# lsm_cpu.net
KiCad netlist of a schematic drawn in EAGLE
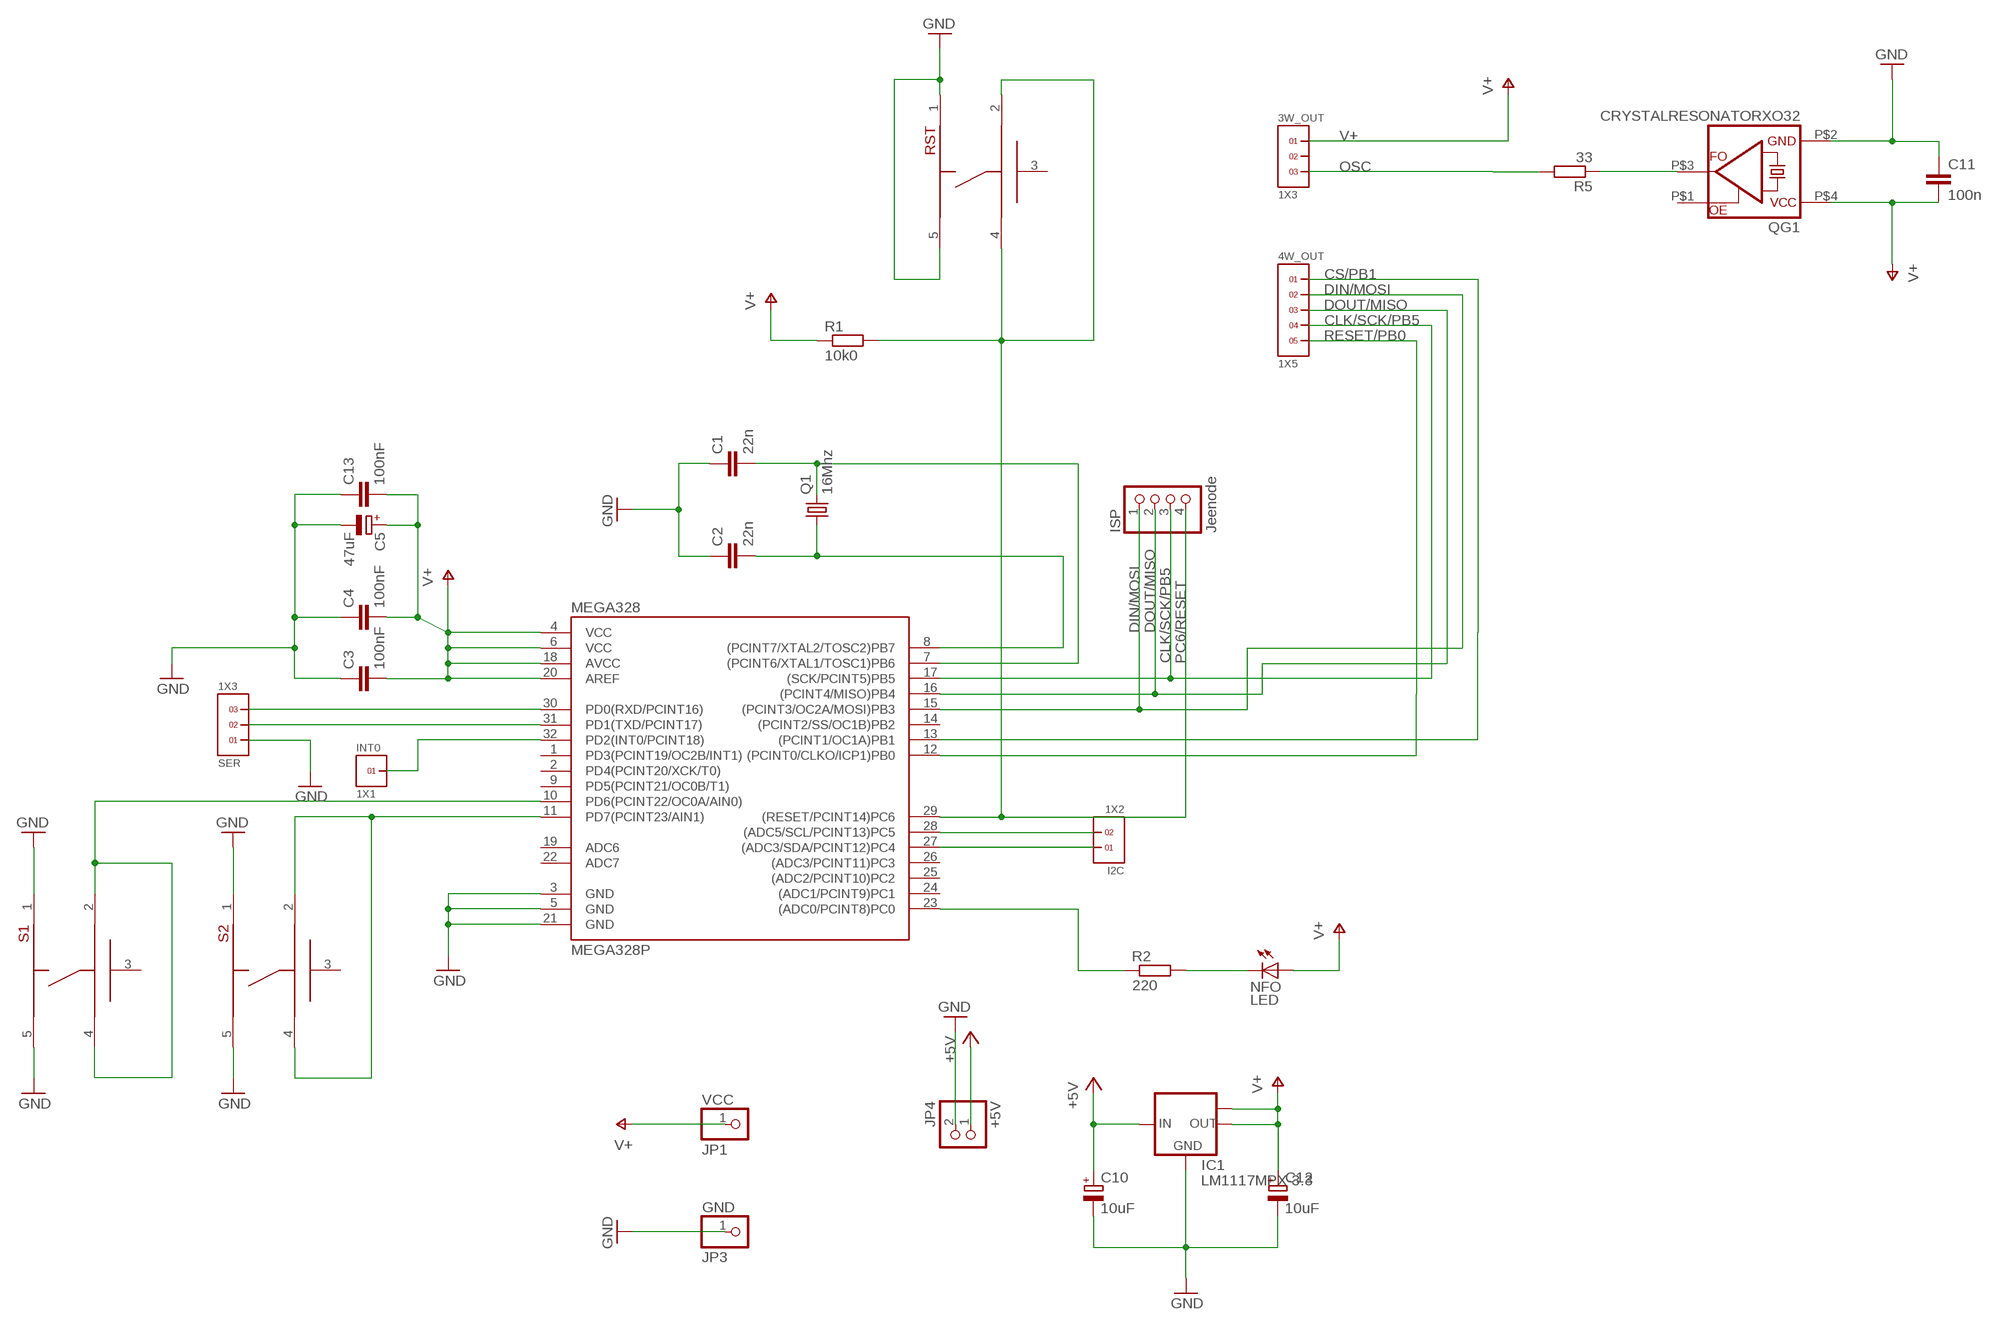
[diagram p0: schematic, sheet 1]

(export (version "E")
  (design (tool "Eeschema 10.0.6"))
  (components
    (comp (ref "+5V")
      (value "JP4")
      (footprint "eagle-import:1X02")
      (libsource (lib "eagle-import") (part "PINHD-1X2"))
    )
    (comp (ref "3W_OUT")
      (value "1X3")
      (footprint "eagle-import:1X3")
      (libsource (lib "eagle-import") (part "1X3"))
    )
    (comp (ref "4W_OUT")
      (value "1X5")
      (footprint "eagle-import:1X5")
      (libsource (lib "eagle-import") (part "1X5"))
    )
    (comp (ref "C1")
      (value "22n")
      (footprint "eagle-import:C1206")
      (libsource (lib "eagle-import") (part "C-EUC1206"))
    )
    (comp (ref "C2")
      (value "22n")
      (footprint "eagle-import:C1206")
      (libsource (lib "eagle-import") (part "C-EUC1206"))
    )
    (comp (ref "C3")
      (value "100nF")
      (footprint "eagle-import:C1206")
      (libsource (lib "eagle-import") (part "C-EUC1206"))
    )
    (comp (ref "C4")
      (value "100nF")
      (footprint "eagle-import:C1206")
      (libsource (lib "eagle-import") (part "C-EUC1206"))
    )
    (comp (ref "C5")
      (value "47uF")
      (footprint "eagle-import:E2-4")
      (libsource (lib "eagle-import") (part "CPOL-EUE2-4"))
    )
    (comp (ref "C10")
      (value "10uF")
      (footprint "eagle-import:E2-4")
      (libsource (lib "eagle-import") (part "CPOL-EUE2-4"))
    )
    (comp (ref "C11")
      (value "100n")
      (footprint "eagle-import:C1206")
      (libsource (lib "eagle-import") (part "C-EUC1206"))
    )
    (comp (ref "C12")
      (value "10uF")
      (footprint "eagle-import:E2-4")
      (libsource (lib "eagle-import") (part "CPOL-EUE2-4"))
    )
    (comp (ref "C13")
      (value "100nF")
      (footprint "eagle-import:C1206")
      (libsource (lib "eagle-import") (part "C-EUC1206"))
    )
    (comp (ref "GND")
      (value "JP3")
      (footprint "eagle-import:1X01")
      (libsource (lib "eagle-import") (part "PINHD-1X1"))
    )
    (comp (ref "I2C")
      (value "1X2")
      (footprint "eagle-import:1X2")
      (libsource (lib "eagle-import") (part "1X2"))
    )
    (comp (ref "IC1")
      (value "LM1117MPX-3.3")
      (footprint "eagle-import:SOT223")
      (libsource (lib "eagle-import") (part "LM1117MPX-3.3"))
    )
    (comp (ref "INT0")
      (value "1X1")
      (footprint "eagle-import:1X1")
      (libsource (lib "eagle-import") (part "1X1"))
    )
    (comp (ref "ISP")
      (value "Jeenode")
      (footprint "eagle-import:1X04")
      (libsource (lib "eagle-import") (part "PINHD-1X4"))
    )
    (comp (ref "MEGA328")
      (value "MEGA328P")
      (footprint "eagle-import:TQFP32-08")
      (libsource (lib "eagle-import") (part "MEGA328P"))
    )
    (comp (ref "NFO")
      (value "LED")
      (footprint "eagle-import:SML1206")
      (libsource (lib "eagle-import") (part "LEDSML1206"))
    )
    (comp (ref "Q1")
      (value "16Mhz")
      (footprint "eagle-import:MT")
      (libsource (lib "eagle-import") (part "CRYSTALMT"))
    )
    (comp (ref "QG1")
      (value "CRYSTALRESONATORXO32")
      (footprint "eagle-import:XO32")
      (libsource (lib "eagle-import") (part "CRYSTALRESONATORXO32"))
    )
    (comp (ref "R1")
      (value "10k0")
      (footprint "eagle-import:R0805")
      (libsource (lib "eagle-import") (part "R-EU_R0805"))
    )
    (comp (ref "R2")
      (value "220")
      (footprint "eagle-import:R0805")
      (libsource (lib "eagle-import") (part "R-EU_R0805"))
    )
    (comp (ref "R5")
      (value "33")
      (footprint "eagle-import:R0805")
      (libsource (lib "eagle-import") (part "R-EU_R0805"))
    )
    (comp (ref "RST")
      (value "KMSXXXG")
      (footprint "eagle-import:C&K-KMS-SWITCH")
      (libsource (lib "eagle-import") (part "KMSXXXG"))
    )
    (comp (ref "S1")
      (value "KMSXXXG")
      (footprint "eagle-import:C&K-KMS-SWITCH")
      (libsource (lib "eagle-import") (part "KMSXXXG"))
    )
    (comp (ref "S2")
      (value "KMSXXXG")
      (footprint "eagle-import:C&K-KMS-SWITCH")
      (libsource (lib "eagle-import") (part "KMSXXXG"))
    )
    (comp (ref "SER")
      (value "1X3")
      (footprint "eagle-import:1X3")
      (libsource (lib "eagle-import") (part "1X3"))
    )
    (comp (ref "VCC")
      (value "JP1")
      (footprint "eagle-import:1X01")
      (libsource (lib "eagle-import") (part "PINHD-1X1"))
    )
  )
  (nets
    (net (code "1") (name "+5V") (class "Default")
      (node (ref "+5V") (pin "1") (pinfunction "1_1") (pintype "passive"))
      (node (ref "C10") (pin "+") (pinfunction "+_+") (pintype "passive"))
      (node (ref "IC1") (pin "3") (pinfunction "IN_3") (pintype "input"))
    )
    (net (code "2") (name "/CLK{slash}SCK{slash}PB5") (class "Default")
      (node (ref "4W_OUT") (pin "4") (pinfunction "4_4") (pintype "bidirectional"))
      (node (ref "ISP") (pin "3") (pinfunction "3_3") (pintype "passive"))
      (node (ref "MEGA328") (pin "17") (pinfunction "(SCK/PCINT5)PB5_17") (pintype "bidirectional"))
    )
    (net (code "3") (name "/CS{slash}PB1") (class "Default")
      (node (ref "4W_OUT") (pin "1") (pinfunction "1_1") (pintype "bidirectional"))
      (node (ref "MEGA328") (pin "13") (pinfunction "(PCINT1/OC1A)PB1_13") (pintype "bidirectional"))
    )
    (net (code "4") (name "/DIN{slash}MOSI") (class "Default")
      (node (ref "4W_OUT") (pin "2") (pinfunction "2_2") (pintype "bidirectional"))
      (node (ref "ISP") (pin "1") (pinfunction "1_1") (pintype "passive"))
      (node (ref "MEGA328") (pin "15") (pinfunction "(PCINT3/OC2A/MOSI)PB3_15") (pintype "bidirectional"))
    )
    (net (code "5") (name "/DOUT{slash}MISO") (class "Default")
      (node (ref "4W_OUT") (pin "3") (pinfunction "3_3") (pintype "bidirectional"))
      (node (ref "ISP") (pin "2") (pinfunction "2_2") (pintype "passive"))
      (node (ref "MEGA328") (pin "16") (pinfunction "(PCINT4/MISO)PB4_16") (pintype "bidirectional"))
    )
    (net (code "6") (name "/OSC") (class "Default")
      (node (ref "3W_OUT") (pin "3") (pinfunction "3_3") (pintype "bidirectional"))
      (node (ref "R5") (pin "2") (pinfunction "2_2") (pintype "passive"))
    )
    (net (code "7") (name "/PC6{slash}RESET") (class "Default")
      (node (ref "ISP") (pin "4") (pinfunction "4_4") (pintype "passive"))
      (node (ref "MEGA328") (pin "29") (pinfunction "(RESET/PCINT14)PC6_29") (pintype "bidirectional"))
      (node (ref "R1") (pin "2") (pinfunction "2_2") (pintype "passive"))
      (node (ref "RST") (pin "2") (pinfunction "2_2") (pintype "bidirectional"))
      (node (ref "RST") (pin "4") (pinfunction "4_4") (pintype "bidirectional"))
    )
    (net (code "8") (name "/RESET{slash}PB0") (class "Default")
      (node (ref "4W_OUT") (pin "5") (pinfunction "5_5") (pintype "bidirectional"))
      (node (ref "MEGA328") (pin "12") (pinfunction "(PCINT0/CLKO/ICP1)PB0_12") (pintype "bidirectional"))
    )
    (net (code "9") (name "GND") (class "Default")
      (node (ref "+5V") (pin "2") (pinfunction "2_2") (pintype "passive"))
      (node (ref "C1") (pin "1") (pinfunction "1_1") (pintype "passive"))
      (node (ref "C10") (pin "-") (pinfunction "-_-") (pintype "passive"))
      (node (ref "C11") (pin "1") (pinfunction "1_1") (pintype "passive"))
      (node (ref "C12") (pin "-") (pinfunction "-_-") (pintype "passive"))
      (node (ref "C13") (pin "1") (pinfunction "1_1") (pintype "passive"))
      (node (ref "C2") (pin "1") (pinfunction "1_1") (pintype "passive"))
      (node (ref "C3") (pin "1") (pinfunction "1_1") (pintype "passive"))
      (node (ref "C4") (pin "1") (pinfunction "1_1") (pintype "passive"))
      (node (ref "C5") (pin "-") (pinfunction "-_-") (pintype "passive"))
      (node (ref "GND") (pin "1") (pinfunction "1_1") (pintype "passive"))
      (node (ref "IC1") (pin "1") (pinfunction "GND_1") (pintype "input"))
      (node (ref "MEGA328") (pin "21") (pinfunction "GND_21") (pintype "power_in"))
      (node (ref "MEGA328") (pin "3") (pinfunction "GND_3") (pintype "power_in"))
      (node (ref "MEGA328") (pin "5") (pinfunction "GND_5") (pintype "power_in"))
      (node (ref "QG1") (pin "P$2") (pinfunction "GND_P$2") (pintype "power_in"))
      (node (ref "RST") (pin "1") (pinfunction "1_1") (pintype "bidirectional"))
      (node (ref "RST") (pin "5") (pinfunction "5_5") (pintype "bidirectional"))
      (node (ref "S1") (pin "1") (pinfunction "1_1") (pintype "bidirectional"))
      (node (ref "S1") (pin "5") (pinfunction "5_5") (pintype "bidirectional"))
      (node (ref "S2") (pin "1") (pinfunction "1_1") (pintype "bidirectional"))
      (node (ref "S2") (pin "5") (pinfunction "5_5") (pintype "bidirectional"))
      (node (ref "SER") (pin "1") (pinfunction "1_1") (pintype "bidirectional"))
    )
    (net (code "10") (name "Net-(MEGA328-(ADC0{slash}PCINT8)PC0)") (class "Default")
      (node (ref "MEGA328") (pin "23") (pinfunction "(ADC0/PCINT8)PC0_23") (pintype "bidirectional"))
      (node (ref "R2") (pin "1") (pinfunction "1_1") (pintype "passive"))
    )
    (net (code "11") (name "Net-(MEGA328-(ADC3{slash}SDA{slash}PCINT12)PC4)") (class "Default")
      (node (ref "I2C") (pin "1") (pinfunction "1_1") (pintype "bidirectional"))
      (node (ref "MEGA328") (pin "27") (pinfunction "(ADC3/SDA/PCINT12)PC4_27") (pintype "bidirectional"))
    )
    (net (code "12") (name "Net-(MEGA328-(ADC5{slash}SCL{slash}PCINT13)PC5)") (class "Default")
      (node (ref "I2C") (pin "2") (pinfunction "2_2") (pintype "bidirectional"))
      (node (ref "MEGA328") (pin "28") (pinfunction "(ADC5/SCL/PCINT13)PC5_28") (pintype "bidirectional"))
    )
    (net (code "13") (name "Net-(MEGA328-(PCINT6{slash}XTAL1{slash}TOSC1)PB6)") (class "Default")
      (node (ref "C1") (pin "2") (pinfunction "2_2") (pintype "passive"))
      (node (ref "MEGA328") (pin "7") (pinfunction "(PCINT6/XTAL1/TOSC1)PB6_7") (pintype "bidirectional"))
      (node (ref "Q1") (pin "P3") (pinfunction "2_P3") (pintype "passive"))
    )
    (net (code "14") (name "Net-(MEGA328-(PCINT7{slash}XTAL2{slash}TOSC2)PB7)") (class "Default")
      (node (ref "C2") (pin "2") (pinfunction "2_2") (pintype "passive"))
      (node (ref "MEGA328") (pin "8") (pinfunction "(PCINT7/XTAL2/TOSC2)PB7_8") (pintype "bidirectional"))
      (node (ref "Q1") (pin "P1") (pinfunction "1_P1") (pintype "passive"))
    )
    (net (code "15") (name "Net-(MEGA328-PD0(RXD{slash}PCINT16))") (class "Default")
      (node (ref "MEGA328") (pin "30") (pinfunction "PD0(RXD/PCINT16)_30") (pintype "bidirectional"))
      (node (ref "SER") (pin "3") (pinfunction "3_3") (pintype "bidirectional"))
    )
    (net (code "16") (name "Net-(MEGA328-PD1(TXD{slash}PCINT17))") (class "Default")
      (node (ref "MEGA328") (pin "31") (pinfunction "PD1(TXD/PCINT17)_31") (pintype "bidirectional"))
      (node (ref "SER") (pin "2") (pinfunction "2_2") (pintype "bidirectional"))
    )
    (net (code "17") (name "Net-(MEGA328-PD2(INT0{slash}PCINT18))") (class "Default")
      (node (ref "INT0") (pin "1") (pinfunction "1_1") (pintype "bidirectional"))
      (node (ref "MEGA328") (pin "32") (pinfunction "PD2(INT0/PCINT18)_32") (pintype "bidirectional"))
    )
    (net (code "18") (name "Net-(MEGA328-PD6(PCINT22{slash}OC0A{slash}AIN0))") (class "Default")
      (node (ref "MEGA328") (pin "10") (pinfunction "PD6(PCINT22/OC0A/AIN0)_10") (pintype "bidirectional"))
      (node (ref "S1") (pin "2") (pinfunction "2_2") (pintype "bidirectional"))
      (node (ref "S1") (pin "4") (pinfunction "4_4") (pintype "bidirectional"))
    )
    (net (code "19") (name "Net-(MEGA328-PD7(PCINT23{slash}AIN1))") (class "Default")
      (node (ref "MEGA328") (pin "11") (pinfunction "PD7(PCINT23/AIN1)_11") (pintype "bidirectional"))
      (node (ref "S2") (pin "2") (pinfunction "2_2") (pintype "bidirectional"))
      (node (ref "S2") (pin "4") (pinfunction "4_4") (pintype "bidirectional"))
    )
    (net (code "20") (name "Net-(NFO-PadC)") (class "Default")
      (node (ref "NFO") (pin "C") (pinfunction "C_C") (pintype "passive"))
      (node (ref "R2") (pin "2") (pinfunction "2_2") (pintype "passive"))
    )
    (net (code "21") (name "Net-(QG1-FO)") (class "Default")
      (node (ref "QG1") (pin "P$3") (pinfunction "FO_P$3") (pintype "output"))
      (node (ref "R5") (pin "1") (pinfunction "1_1") (pintype "passive"))
    )
    (net (code "22") (name "V+") (class "Default")
      (node (ref "3W_OUT") (pin "1") (pinfunction "1_1") (pintype "bidirectional"))
      (node (ref "C11") (pin "2") (pinfunction "2_2") (pintype "passive"))
      (node (ref "C12") (pin "+") (pinfunction "+_+") (pintype "passive"))
      (node (ref "C13") (pin "2") (pinfunction "2_2") (pintype "passive"))
      (node (ref "C3") (pin "2") (pinfunction "2_2") (pintype "passive"))
      (node (ref "C4") (pin "2") (pinfunction "2_2") (pintype "passive"))
      (node (ref "C5") (pin "+") (pinfunction "+_+") (pintype "passive"))
      (node (ref "IC1") (pin "2") (pinfunction "OUT_2") (pintype "passive"))
      (node (ref "IC1") (pin "TAB") (pinfunction "OUT1_TAB") (pintype "passive"))
      (node (ref "MEGA328") (pin "18") (pinfunction "AVCC_18") (pintype "power_in"))
      (node (ref "MEGA328") (pin "20") (pinfunction "AREF_20") (pintype "power_in"))
      (node (ref "MEGA328") (pin "4") (pinfunction "VCC_4") (pintype "power_in"))
      (node (ref "MEGA328") (pin "6") (pinfunction "VCC_6") (pintype "power_in"))
      (node (ref "NFO") (pin "A") (pinfunction "A_A") (pintype "passive"))
      (node (ref "QG1") (pin "P$4") (pinfunction "VCC_P$4") (pintype "power_in"))
      (node (ref "R1") (pin "1") (pinfunction "1_1") (pintype "passive"))
      (node (ref "VCC") (pin "1") (pinfunction "1_1") (pintype "passive"))
    )
    (net (code "23") (name "unconnected-(3W_OUT-Pad2)") (class "Default")
      (node (ref "3W_OUT") (pin "2") (pinfunction "2_2") (pintype "bidirectional"))
    )
    (net (code "24") (name "unconnected-(MEGA328-(ADC1{slash}PCINT9)PC1-Pad24)") (class "Default")
      (node (ref "MEGA328") (pin "24") (pinfunction "(ADC1/PCINT9)PC1_24") (pintype "bidirectional"))
    )
    (net (code "25") (name "unconnected-(MEGA328-(ADC2{slash}PCINT10)PC2-Pad25)") (class "Default")
      (node (ref "MEGA328") (pin "25") (pinfunction "(ADC2/PCINT10)PC2_25") (pintype "bidirectional"))
    )
    (net (code "26") (name "unconnected-(MEGA328-(ADC3{slash}PCINT11)PC3-Pad26)") (class "Default")
      (node (ref "MEGA328") (pin "26") (pinfunction "(ADC3/PCINT11)PC3_26") (pintype "bidirectional"))
    )
    (net (code "27") (name "unconnected-(MEGA328-(PCINT2{slash}SS{slash}OC1B)PB2-Pad14)") (class "Default")
      (node (ref "MEGA328") (pin "14") (pinfunction "(PCINT2/SS/OC1B)PB2_14") (pintype "bidirectional"))
    )
    (net (code "28") (name "unconnected-(MEGA328-ADC6-Pad19)") (class "Default")
      (node (ref "MEGA328") (pin "19") (pinfunction "ADC6_19") (pintype "input"))
    )
    (net (code "29") (name "unconnected-(MEGA328-ADC7-Pad22)") (class "Default")
      (node (ref "MEGA328") (pin "22") (pinfunction "ADC7_22") (pintype "input"))
    )
    (net (code "30") (name "unconnected-(MEGA328-PD3(PCINT19{slash}OC2B{slash}INT1)-Pad1)") (class "Default")
      (node (ref "MEGA328") (pin "1") (pinfunction "PD3(PCINT19/OC2B/INT1)_1") (pintype "bidirectional"))
    )
    (net (code "31") (name "unconnected-(MEGA328-PD4(PCINT20{slash}XCK{slash}T0)-Pad2)") (class "Default")
      (node (ref "MEGA328") (pin "2") (pinfunction "PD4(PCINT20/XCK/T0)_2") (pintype "bidirectional"))
    )
    (net (code "32") (name "unconnected-(MEGA328-PD5(PCINT21{slash}OC0B{slash}T1)-Pad9)") (class "Default")
      (node (ref "MEGA328") (pin "9") (pinfunction "PD5(PCINT21/OC0B/T1)_9") (pintype "bidirectional"))
    )
    (net (code "33") (name "unconnected-(QG1-OE-PadP$1)") (class "Default")
      (node (ref "QG1") (pin "P$1") (pinfunction "OE_P$1") (pintype "input"))
    )
    (net (code "34") (name "unconnected-(RST-Pad3)") (class "Default")
      (node (ref "RST") (pin "3") (pinfunction "3_3") (pintype "bidirectional"))
    )
    (net (code "35") (name "unconnected-(S1-Pad3)") (class "Default")
      (node (ref "S1") (pin "3") (pinfunction "3_3") (pintype "bidirectional"))
    )
    (net (code "36") (name "unconnected-(S2-Pad3)") (class "Default")
      (node (ref "S2") (pin "3") (pinfunction "3_3") (pintype "bidirectional"))
    )
  )
)
